# spiflash.net
KiCad netlist of a schematic drawn in Altium Designer
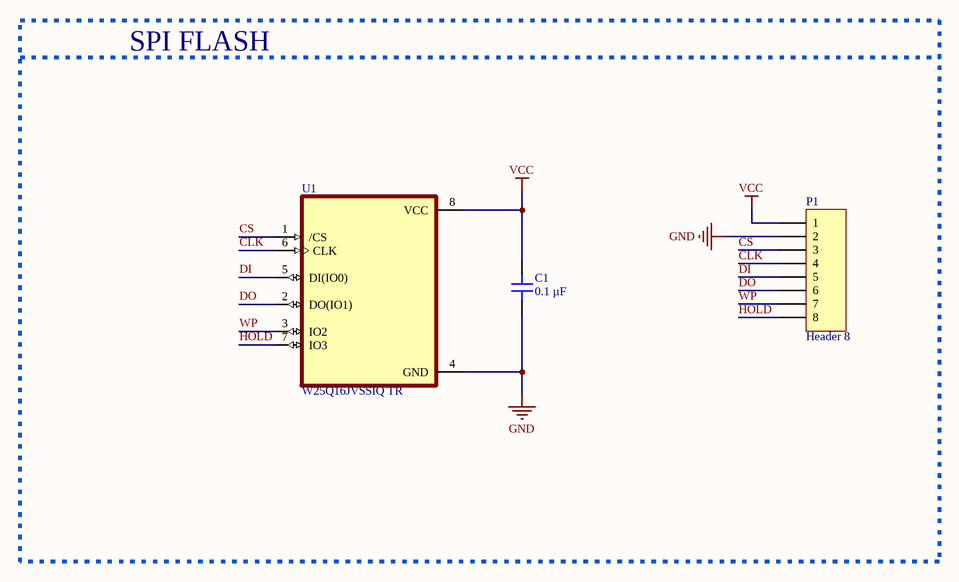
[diagram p0: spiflash.SchDoc]

(export (version "E")
  (design (tool "Eeschema 10.0.6"))
  (components
    (comp (ref "C1")
      (value "0.1 µF")
      (footprint "CAP 0805_2012")
      (description "CAP CER 0.1UF 50V X7R 0805")
      (fields (field (name "PART NUMBER") "CC0805MRX7R9BB104") (field (name "MANUFACTURER") "Yageo"))
      (libsource (lib "Celestial Altium Library - altium_library") (part "Capacitor"))
    )
    (comp (ref "P1")
      (value "Header 8")
      (footprint "HDR1X8")
      (description "Header, 8-Pin")
      (fields (field (name "PUBLISHER") "Altium Limited"))
      (libsource (lib "Miscellaneous Connectors") (part "Header 8"))
    )
    (comp (ref "U1")
      (value "W25Q16JVSSIQ TR")
      (footprint "SOIC127P790X216-8N")
      (description "IC FLASH 16MBIT SPI/QUAD 8SOIC")
      (fields
        (field (name "MANUFACTURER") "Winbond Electronics")
        (field (name "DIGIKEY PART NUMBER") "W25Q16JVSSIQTR-ND")
      )
      (libsource (lib "canbus") (part "W25Q16JVSSIQ TR"))
    )
  )
  (nets
    (net (code "1") (name "/CLK") (class "Default")
      (node (ref "P1") (pin "4") (pinfunction "4_4") (pintype "passive"))
      (node (ref "U1") (pin "6") (pinfunction "CLK_6") (pintype "input"))
    )
    (net (code "2") (name "/CS") (class "Default")
      (node (ref "P1") (pin "3") (pinfunction "3_3") (pintype "passive"))
      (node (ref "U1") (pin "1") (pinfunction "/CS_1") (pintype "input"))
    )
    (net (code "3") (name "/DI") (class "Default")
      (node (ref "P1") (pin "5") (pinfunction "5_5") (pintype "passive"))
      (node (ref "U1") (pin "5") (pinfunction "DI(IO0)_5") (pintype "bidirectional"))
    )
    (net (code "4") (name "/DO") (class "Default")
      (node (ref "P1") (pin "6") (pinfunction "6_6") (pintype "passive"))
      (node (ref "U1") (pin "2") (pinfunction "DO(IO1)_2") (pintype "bidirectional"))
    )
    (net (code "5") (name "/HOLD") (class "Default")
      (node (ref "P1") (pin "8") (pinfunction "8_8") (pintype "passive"))
      (node (ref "U1") (pin "7") (pinfunction "IO3_7") (pintype "bidirectional"))
    )
    (net (code "6") (name "/WP") (class "Default")
      (node (ref "P1") (pin "7") (pinfunction "7_7") (pintype "passive"))
      (node (ref "U1") (pin "3") (pinfunction "IO2_3") (pintype "bidirectional"))
    )
    (net (code "7") (name "GND") (class "Default")
      (node (ref "C1") (pin "1") (pinfunction "1_1") (pintype "passive"))
      (node (ref "P1") (pin "2") (pinfunction "2_2") (pintype "passive"))
      (node (ref "U1") (pin "4") (pinfunction "GND_4") (pintype "power_in"))
    )
    (net (code "8") (name "VCC") (class "Default")
      (node (ref "C1") (pin "2") (pinfunction "2_2") (pintype "passive"))
      (node (ref "P1") (pin "1") (pinfunction "1_1") (pintype "passive"))
      (node (ref "U1") (pin "8") (pinfunction "VCC_8") (pintype "power_in"))
    )
  )
)
